# 3_3_Voltage_Regulator.net
KiCad netlist of a schematic drawn in Altium Designer
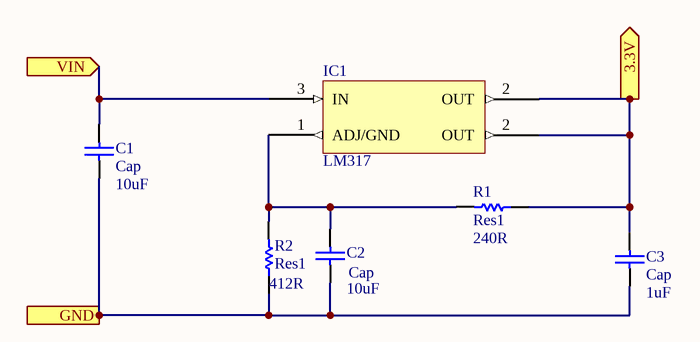
[diagram p0: 3.3 Voltage Regulator.SchDoc]

(export (version "E")
  (design (tool "Eeschema 10.0.6"))
  (components
    (comp (ref "C1")
      (value "Cap")
      (footprint "RAD-0.3")
      (description "Capacitor")
      (fields (field (name "ALTIUM_VALUE") "10uF") (field (name "PUBLISHER") "Altium Limited"))
      (libsource (lib "Miscellaneous Devices") (part "Cap"))
    )
    (comp (ref "C2")
      (value "Cap")
      (footprint "RAD-0.3")
      (description "Capacitor")
      (fields (field (name "ALTIUM_VALUE") "10uF") (field (name "PUBLISHER") "Altium Limited"))
      (libsource (lib "Miscellaneous Devices") (part "Cap"))
    )
    (comp (ref "C3")
      (value "Cap")
      (footprint "RAD-0.3")
      (description "Capacitor")
      (fields (field (name "ALTIUM_VALUE") "1uF") (field (name "PUBLISHER") "Altium Limited"))
      (libsource (lib "Miscellaneous Devices") (part "Cap"))
    )
    (comp (ref "IC1")
      (value "LM317")
      (footprint "SOT-223")
      (libsource (lib "MainboardSchLib") (part "LM317"))
    )
    (comp (ref "R1")
      (value "Res1")
      (footprint "AXIAL-0.3")
      (description "Resistor")
      (fields (field (name "ALTIUM_VALUE") "240R") (field (name "PUBLISHER") "Altium Limited"))
      (libsource (lib "Miscellaneous Devices") (part "Res1"))
    )
    (comp (ref "R2")
      (value "Res1")
      (footprint "AXIAL-0.3")
      (description "Resistor")
      (fields (field (name "ALTIUM_VALUE") "412R") (field (name "PUBLISHER") "Altium Limited"))
      (libsource (lib "Miscellaneous Devices") (part "Res1"))
    )
  )
  (nets
    (net (code "1") (name "/3.3V") (class "Default")
      (node (ref "C3") (pin "2") (pinfunction "2_2") (pintype "passive"))
      (node (ref "IC1") (pin "2") (pinfunction "OUT_2") (pintype "output"))
      (node (ref "R1") (pin "1") (pinfunction "1_1") (pintype "passive"))
    )
    (net (code "2") (name "/GND") (class "Default")
      (node (ref "C1") (pin "1") (pinfunction "1_1") (pintype "passive"))
      (node (ref "C2") (pin "1") (pinfunction "1_1") (pintype "passive"))
      (node (ref "C3") (pin "1") (pinfunction "1_1") (pintype "passive"))
      (node (ref "R2") (pin "1") (pinfunction "1_1") (pintype "passive"))
    )
    (net (code "3") (name "/VIN") (class "Default")
      (node (ref "C1") (pin "2") (pinfunction "2_2") (pintype "passive"))
      (node (ref "IC1") (pin "3") (pinfunction "IN_3") (pintype "input"))
    )
    (net (code "4") (name "Net-(IC1-ADJ{slash}GND)") (class "Default")
      (node (ref "C2") (pin "2") (pinfunction "2_2") (pintype "passive"))
      (node (ref "IC1") (pin "1") (pinfunction "ADJ/GND_1") (pintype "output"))
      (node (ref "R1") (pin "2") (pinfunction "2_2") (pintype "passive"))
      (node (ref "R2") (pin "2") (pinfunction "2_2") (pintype "passive"))
    )
  )
)
